# Sensact_v4_1.net
KiCad netlist of a schematic drawn in EAGLE
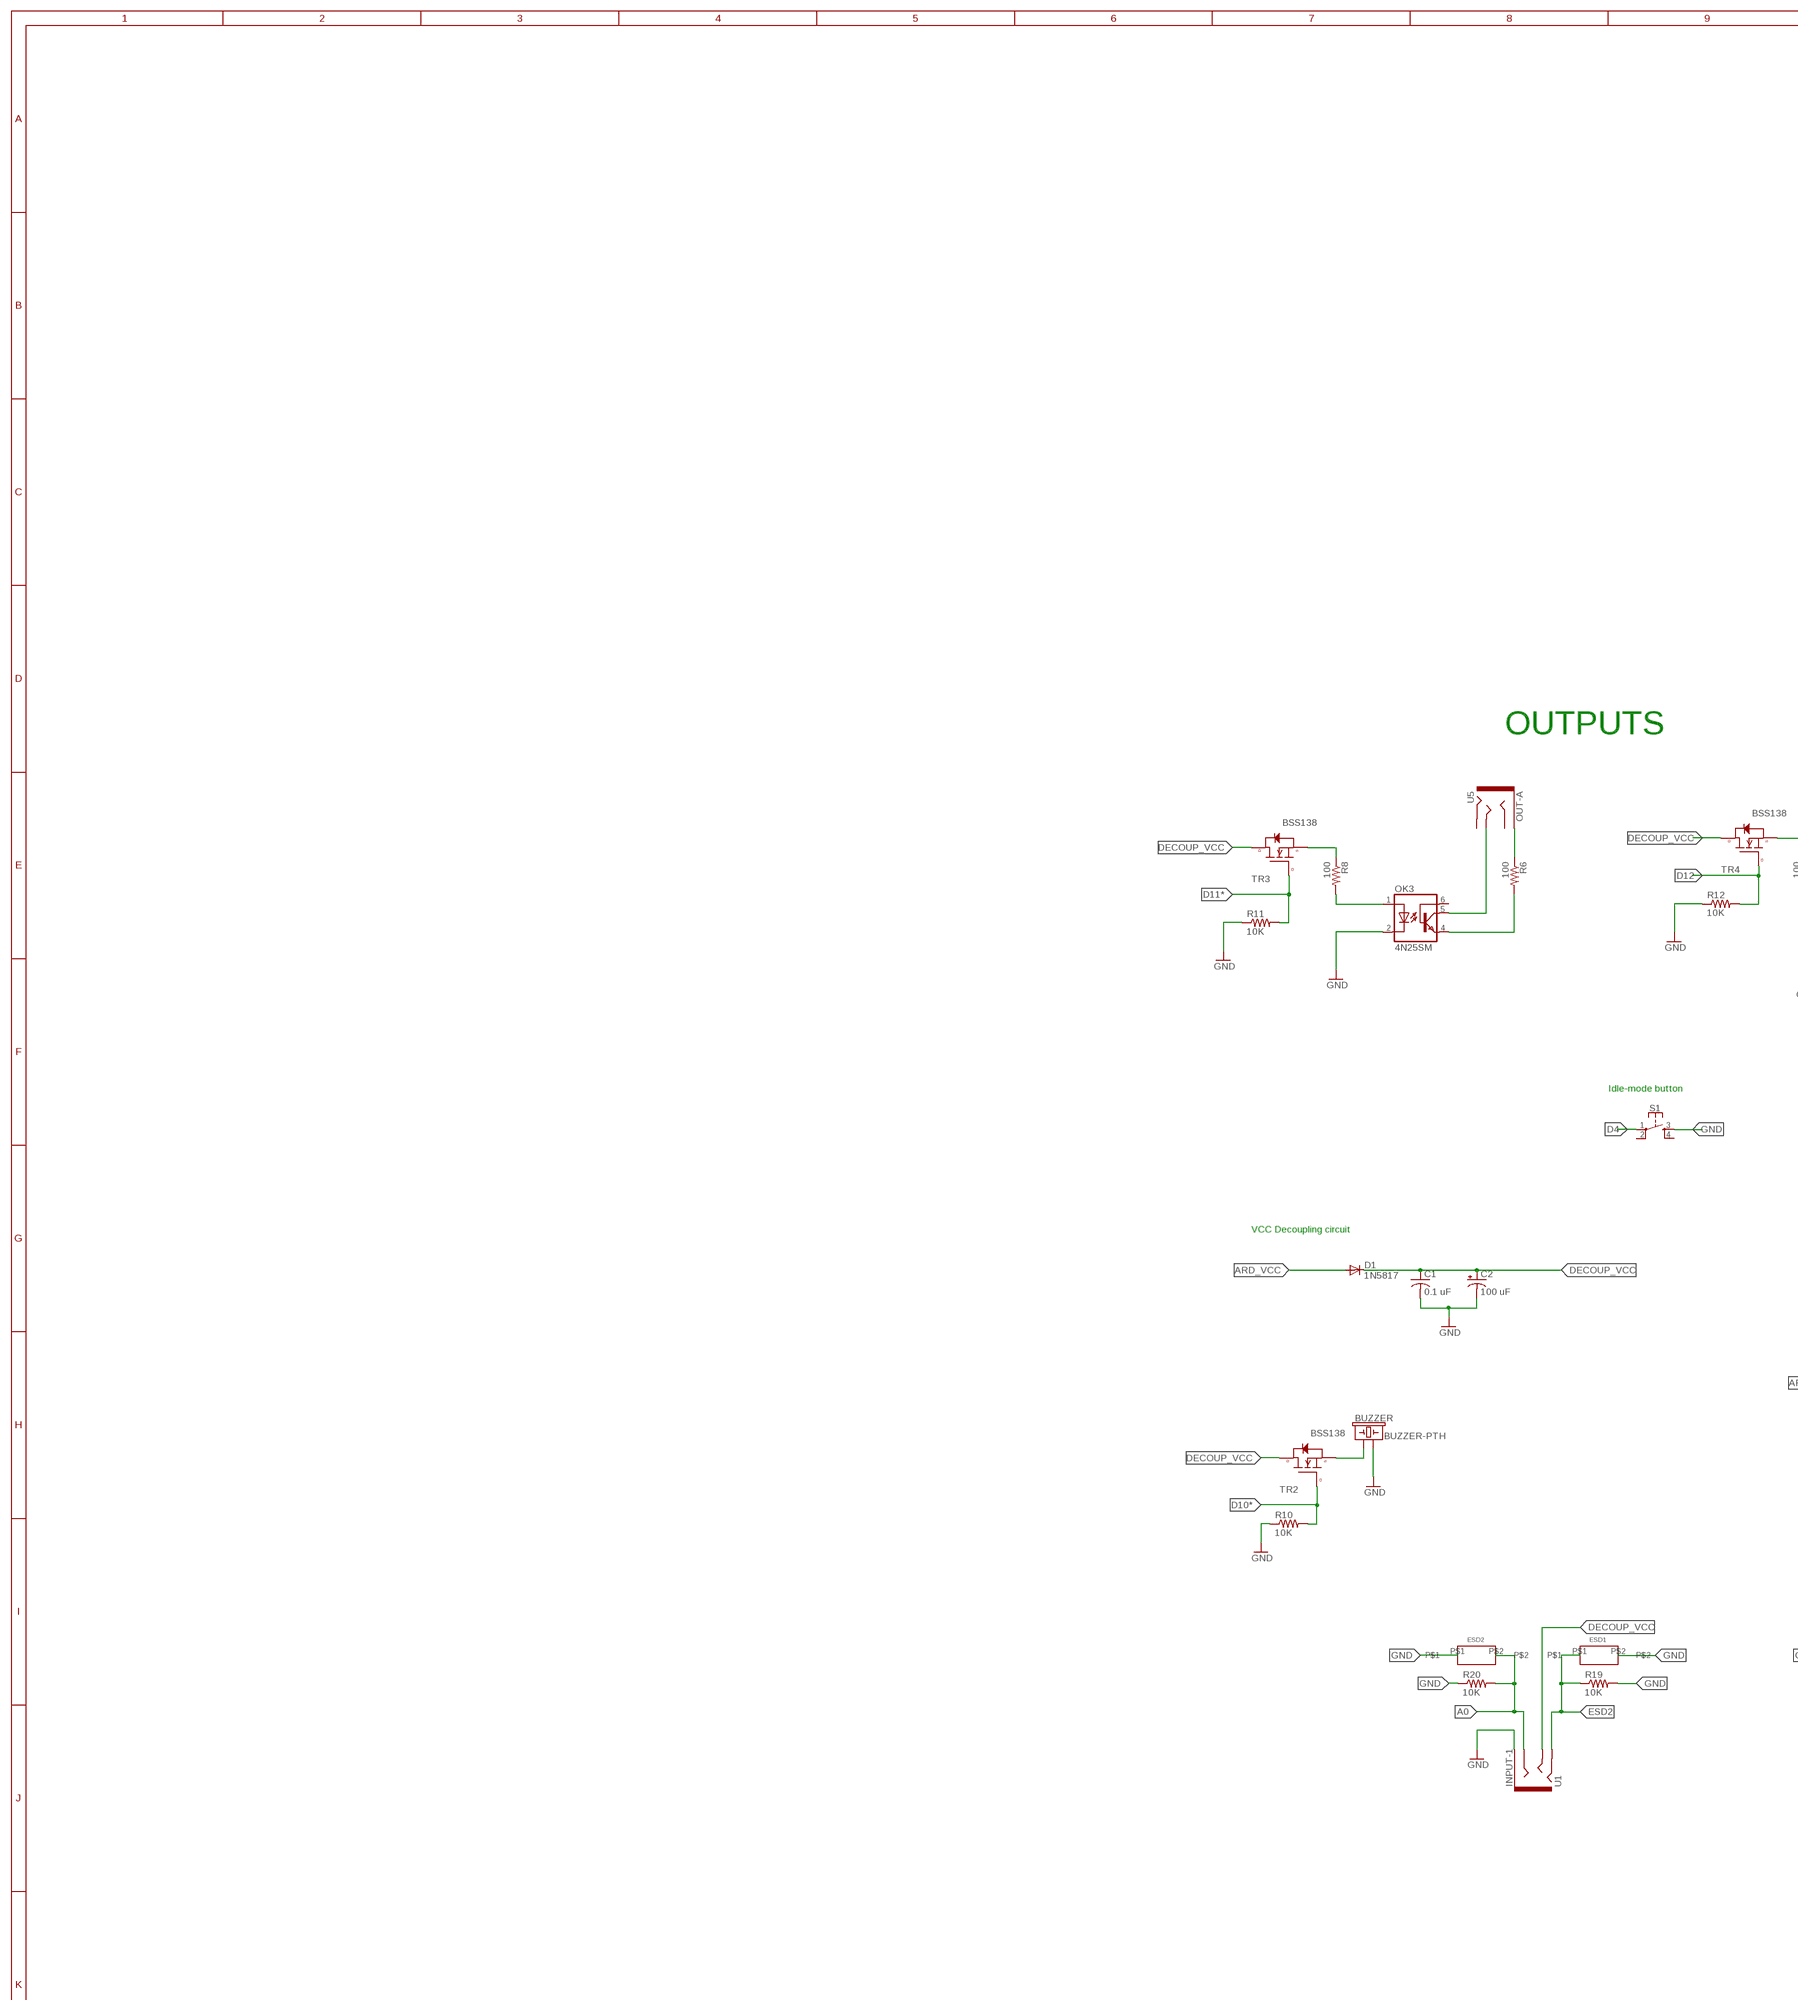
[diagram p0: schematic, sheet 1, part 1 of 3]
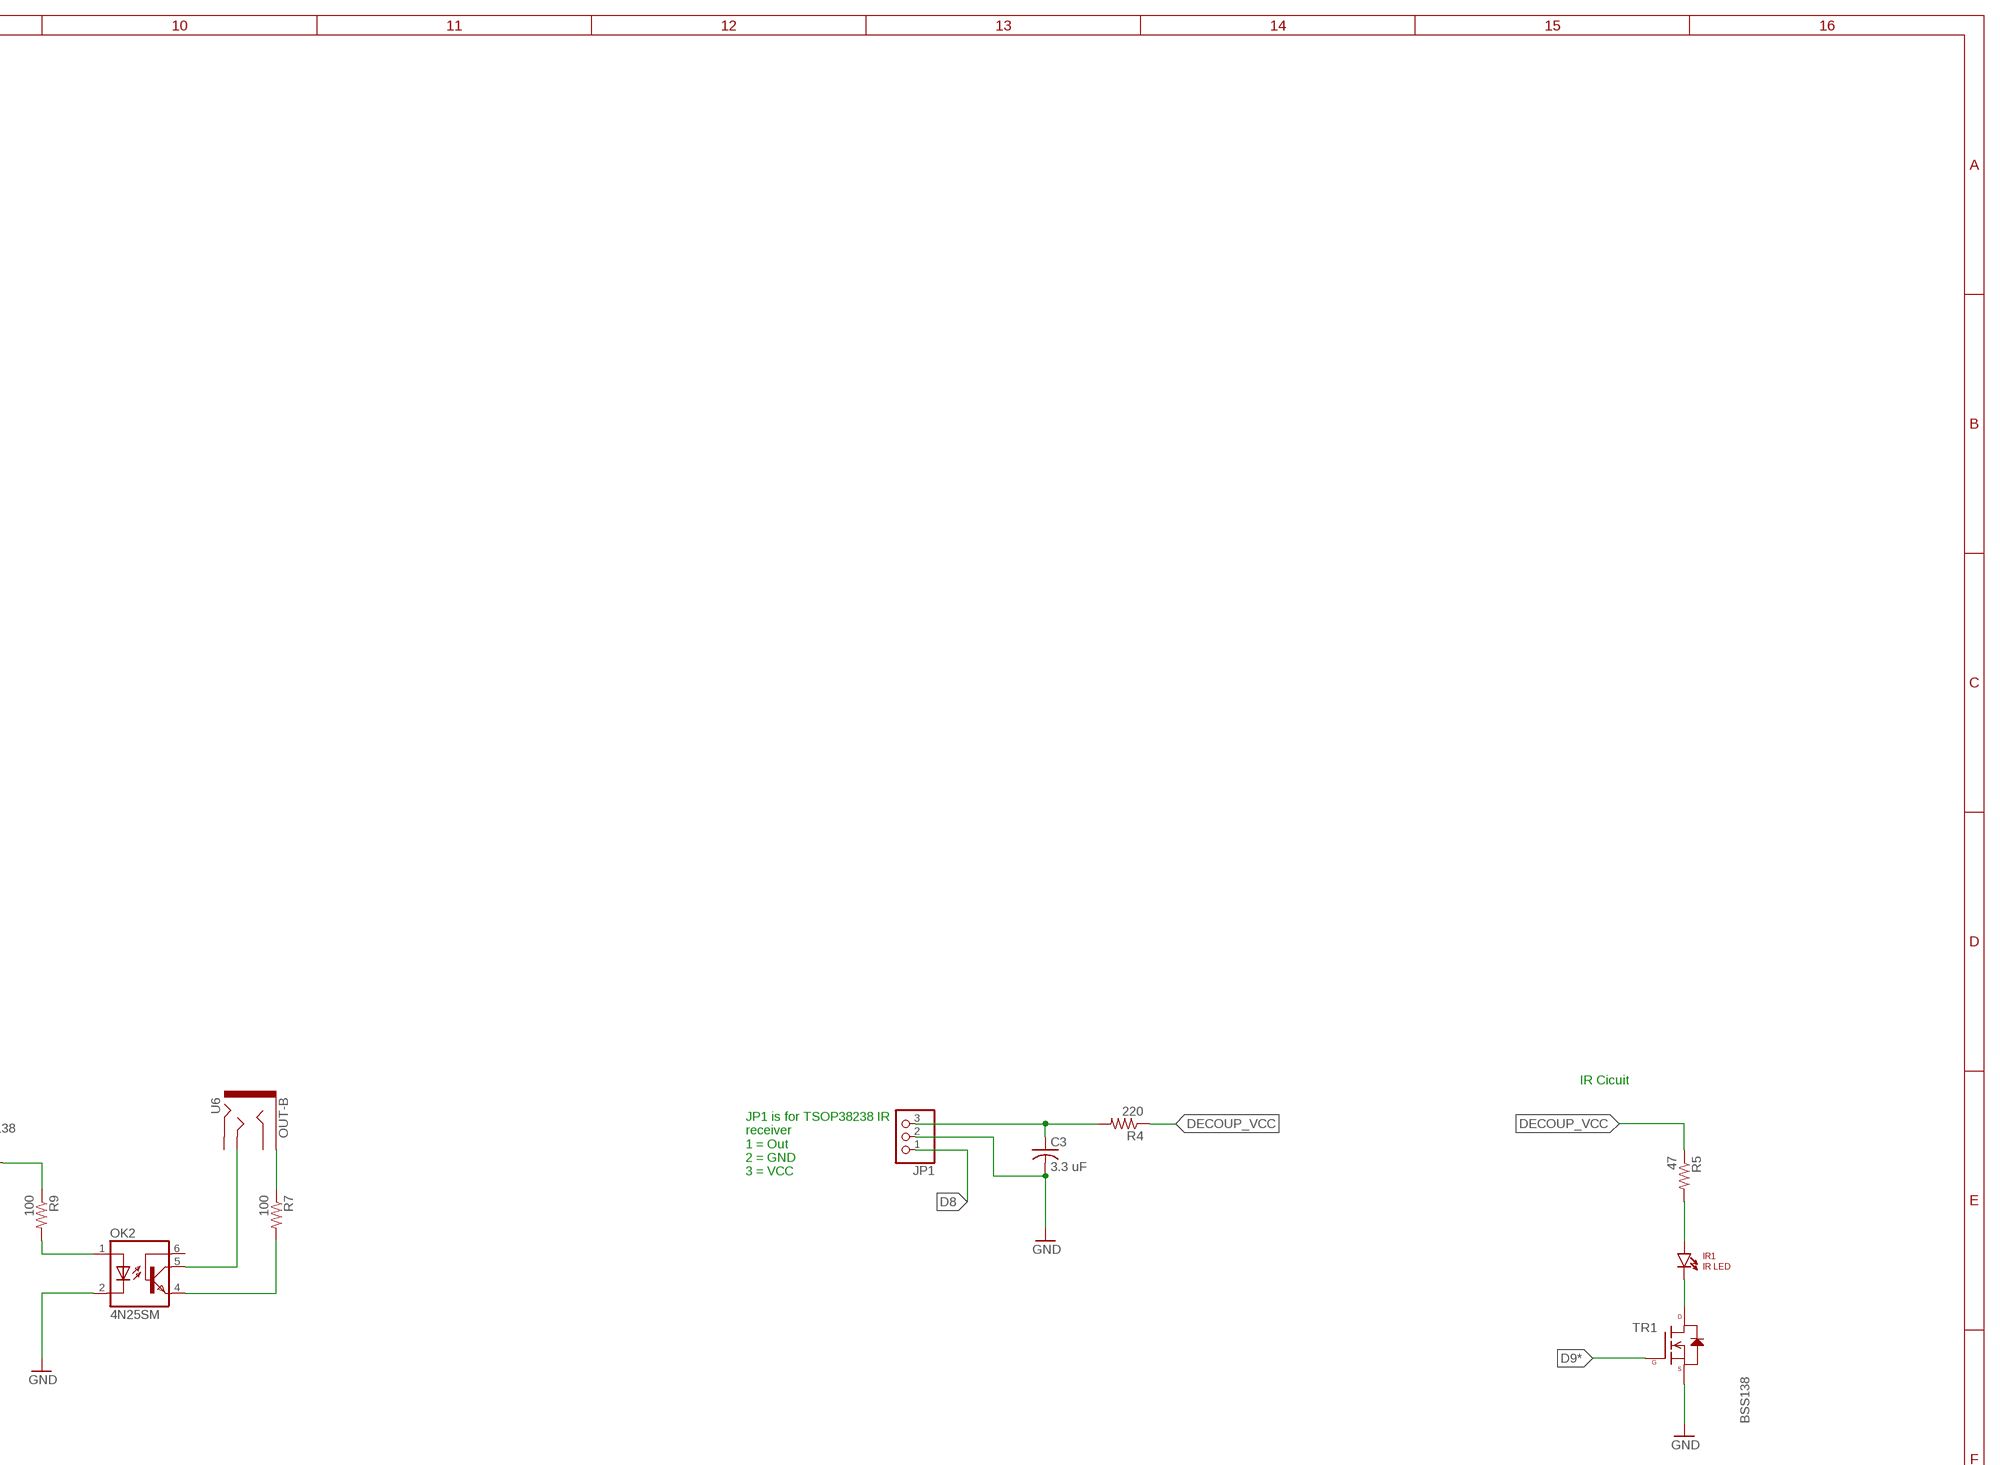
[diagram p1: schematic, sheet 1, part 2 of 3]
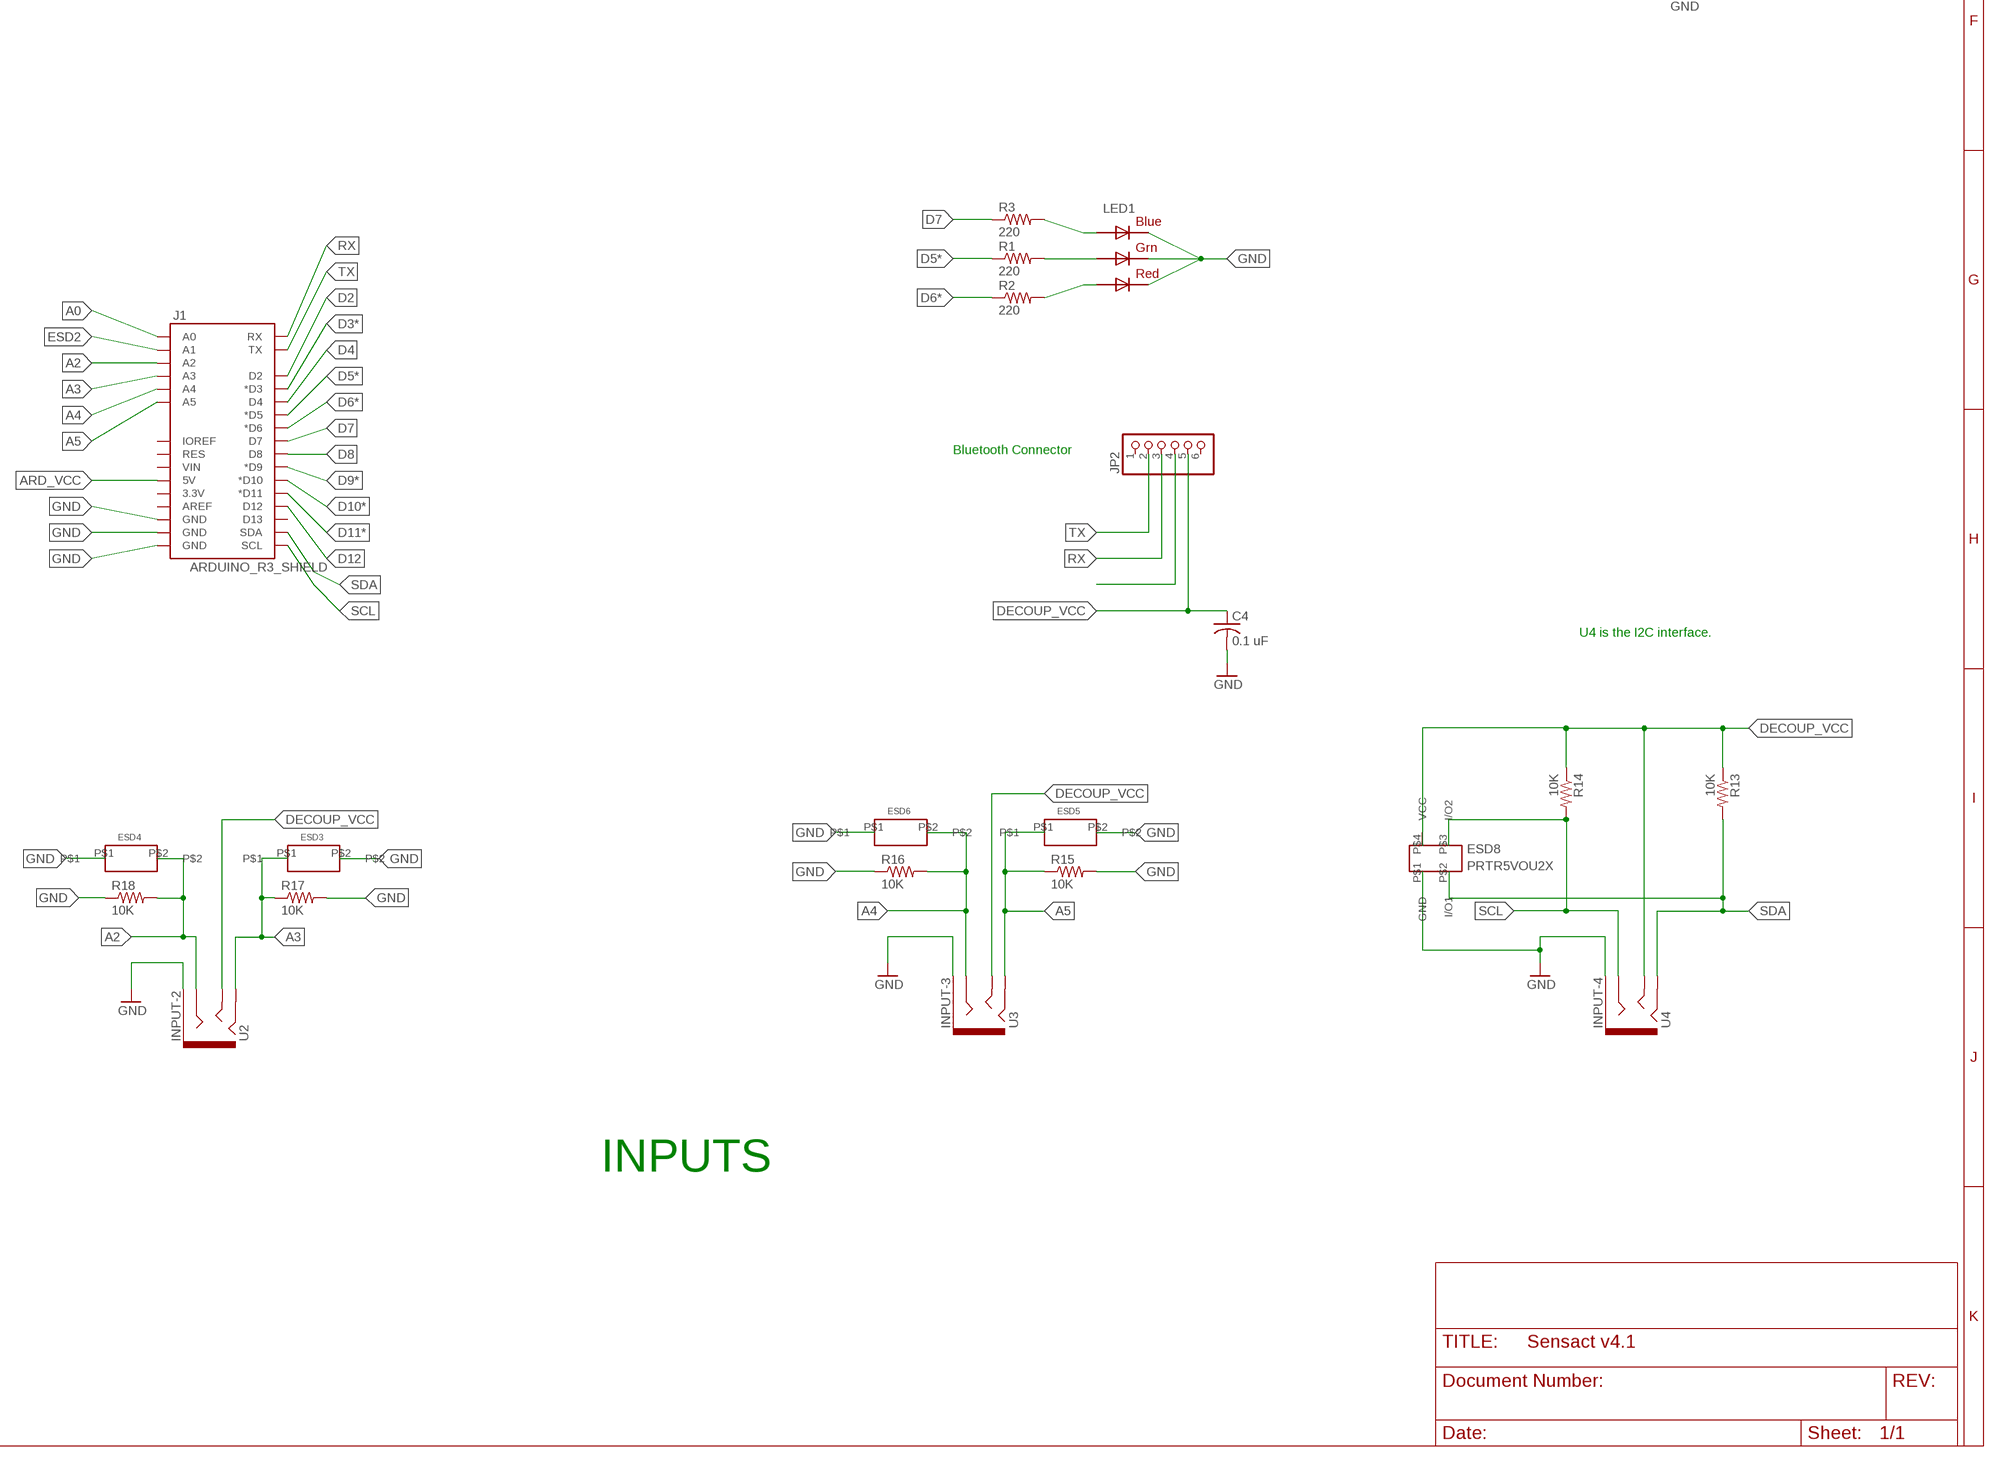
[diagram p2: schematic, sheet 1, part 3 of 3]

(export (version "E")
  (design (tool "Eeschema 10.0.6"))
  (components
    (comp (ref "BUZZER")
      (value "BUZZER-PTH")
      (footprint "eagle-import:BUZZER-12MM")
      (libsource (lib "eagle-import") (part "BUZZER-PTH"))
    )
    (comp (ref "C1")
      (value "0.1 uF")
      (footprint "eagle-import:C0805")
      (libsource (lib "eagle-import") (part "C-USC0805"))
    )
    (comp (ref "C2")
      (value "100 uF")
      (footprint "eagle-import:PANASONIC_C")
      (libsource (lib "eagle-import") (part "CAP_POLC"))
    )
    (comp (ref "C3")
      (value "3.3 uF")
      (footprint "eagle-import:C0805")
      (libsource (lib "eagle-import") (part "C-USC0805"))
    )
    (comp (ref "C4")
      (value "0.1 uF")
      (footprint "eagle-import:C0805")
      (libsource (lib "eagle-import") (part "C-USC0805"))
    )
    (comp (ref "D1")
      (value "1N5817")
      (footprint "eagle-import:DO214AC")
      (libsource (lib "eagle-import") (part "DIODE-DO214AC"))
    )
    (comp (ref "ESD1")
      (value "PESD5V0S1BA")
      (footprint "eagle-import:SOD323")
      (libsource (lib "eagle-import") (part "PESD5V0S1BA"))
    )
    (comp (ref "ESD2")
      (value "PESD5V0S1BA")
      (footprint "eagle-import:SOD323")
      (libsource (lib "eagle-import") (part "PESD5V0S1BA"))
    )
    (comp (ref "ESD3")
      (value "PESD5V0S1BA")
      (footprint "eagle-import:SOD323")
      (libsource (lib "eagle-import") (part "PESD5V0S1BA"))
    )
    (comp (ref "ESD4")
      (value "PESD5V0S1BA")
      (footprint "eagle-import:SOD323")
      (libsource (lib "eagle-import") (part "PESD5V0S1BA"))
    )
    (comp (ref "ESD5")
      (value "PESD5V0S1BA")
      (footprint "eagle-import:SOD323")
      (libsource (lib "eagle-import") (part "PESD5V0S1BA"))
    )
    (comp (ref "ESD6")
      (value "PESD5V0S1BA")
      (footprint "eagle-import:SOD323")
      (libsource (lib "eagle-import") (part "PESD5V0S1BA"))
    )
    (comp (ref "ESD8")
      (value "PRTR5VOU2X")
      (footprint "eagle-import:215")
      (libsource (lib "eagle-import") (part "PRTR5VOU2X"))
    )
    (comp (ref "INPUT-1")
      (value "U1")
      (footprint "eagle-import:AUDIO-JACK-TRRS-THRUHOLE")
      (libsource (lib "eagle-import") (part "AUDIO-JACK-TRRS-THRUHOLE"))
    )
    (comp (ref "INPUT-2")
      (value "U2")
      (footprint "eagle-import:AUDIO-JACK-TRRS-THRUHOLE")
      (libsource (lib "eagle-import") (part "AUDIO-JACK-TRRS-THRUHOLE"))
    )
    (comp (ref "INPUT-3")
      (value "U3")
      (footprint "eagle-import:AUDIO-JACK-TRRS-THRUHOLE")
      (libsource (lib "eagle-import") (part "AUDIO-JACK-TRRS-THRUHOLE"))
    )
    (comp (ref "INPUT-4")
      (value "U4")
      (footprint "eagle-import:AUDIO-JACK-TRRS-THRUHOLE")
      (libsource (lib "eagle-import") (part "AUDIO-JACK-TRRS-THRUHOLE"))
    )
    (comp (ref "IR1")
      (value "IR LED")
      (footprint "eagle-import:LTE-302")
      (libsource (lib "eagle-import") (part "LTE-302"))
    )
    (comp (ref "J1")
      (value "ARDUINO_R3_SHIELD")
      (footprint "eagle-import:UNO_R3_SHIELD")
      (libsource (lib "eagle-import") (part "ARDUINO_R3_SHIELD"))
    )
    (comp (ref "JP1")
      (value "PINHD-1X3")
      (footprint "eagle-import:1X03")
      (libsource (lib "eagle-import") (part "PINHD-1X3"))
    )
    (comp (ref "JP2")
      (value "PINHD-1X6")
      (footprint "eagle-import:1X06")
      (libsource (lib "eagle-import") (part "PINHD-1X6"))
    )
    (comp (ref "LED1")
      (value "RGBLED5050")
      (footprint "eagle-import:RGBLED5050")
      (libsource (lib "eagle-import") (part "RGBLED5050"))
    )
    (comp (ref "OK2")
      (value "4N25SM")
      (footprint "eagle-import:DIL6-SMD")
      (fields (field (name "MF") "FAIRCHILD SEMICONDUCTOR"))
      (libsource (lib "eagle-import") (part "4N?MS25"))
    )
    (comp (ref "OK3")
      (value "4N25SM")
      (footprint "eagle-import:DIL6-SMD")
      (fields (field (name "MF") "FAIRCHILD SEMICONDUCTOR"))
      (libsource (lib "eagle-import") (part "4N?MS25"))
    )
    (comp (ref "OUT-A")
      (value "U5")
      (footprint "eagle-import:AUDIO-JACK-TRRS-THRUHOLE")
      (libsource (lib "eagle-import") (part "AUDIO-JACK-TRRS-THRUHOLE"))
    )
    (comp (ref "OUT-B")
      (value "U6")
      (footprint "eagle-import:AUDIO-JACK-TRRS-THRUHOLE")
      (libsource (lib "eagle-import") (part "AUDIO-JACK-TRRS-THRUHOLE"))
    )
    (comp (ref "R1")
      (value "220")
      (footprint "eagle-import:0805")
      (libsource (lib "eagle-import") (part "RESISTOR0805-RES"))
    )
    (comp (ref "R2")
      (value "220")
      (footprint "eagle-import:0805")
      (libsource (lib "eagle-import") (part "RESISTOR0805-RES"))
    )
    (comp (ref "R3")
      (value "220")
      (footprint "eagle-import:0805")
      (libsource (lib "eagle-import") (part "RESISTOR0805-RES"))
    )
    (comp (ref "R4")
      (value "220")
      (footprint "eagle-import:0805")
      (libsource (lib "eagle-import") (part "RESISTOR0805-RES"))
    )
    (comp (ref "R5")
      (value "47")
      (footprint "eagle-import:0805")
      (libsource (lib "eagle-import") (part "RESISTOR0805-RES"))
    )
    (comp (ref "R6")
      (value "100")
      (footprint "eagle-import:0805")
      (libsource (lib "eagle-import") (part "RESISTOR0805-RES"))
    )
    (comp (ref "R7")
      (value "100")
      (footprint "eagle-import:0805")
      (libsource (lib "eagle-import") (part "RESISTOR0805-RES"))
    )
    (comp (ref "R8")
      (value "100")
      (footprint "eagle-import:0805")
      (libsource (lib "eagle-import") (part "RESISTOR0805-RES"))
    )
    (comp (ref "R9")
      (value "100")
      (footprint "eagle-import:0805")
      (libsource (lib "eagle-import") (part "RESISTOR0805-RES"))
    )
    (comp (ref "R10")
      (value "10K")
      (footprint "eagle-import:0805")
      (libsource (lib "eagle-import") (part "RESISTOR0805-RES"))
    )
    (comp (ref "R11")
      (value "10K")
      (footprint "eagle-import:0805")
      (libsource (lib "eagle-import") (part "RESISTOR0805-RES"))
    )
    (comp (ref "R12")
      (value "10K")
      (footprint "eagle-import:0805")
      (libsource (lib "eagle-import") (part "RESISTOR0805-RES"))
    )
    (comp (ref "R13")
      (value "10K")
      (footprint "eagle-import:0805")
      (libsource (lib "eagle-import") (part "RESISTOR0805-RES"))
    )
    (comp (ref "R14")
      (value "10K")
      (footprint "eagle-import:0805")
      (libsource (lib "eagle-import") (part "RESISTOR0805-RES"))
    )
    (comp (ref "R15")
      (value "10K")
      (footprint "eagle-import:0805")
      (libsource (lib "eagle-import") (part "RESISTOR0805-RES"))
    )
    (comp (ref "R16")
      (value "10K")
      (footprint "eagle-import:0805")
      (libsource (lib "eagle-import") (part "RESISTOR0805-RES"))
    )
    (comp (ref "R17")
      (value "10K")
      (footprint "eagle-import:0805")
      (libsource (lib "eagle-import") (part "RESISTOR0805-RES"))
    )
    (comp (ref "R18")
      (value "10K")
      (footprint "eagle-import:0805")
      (libsource (lib "eagle-import") (part "RESISTOR0805-RES"))
    )
    (comp (ref "R19")
      (value "10K")
      (footprint "eagle-import:0805")
      (libsource (lib "eagle-import") (part "RESISTOR0805-RES"))
    )
    (comp (ref "R20")
      (value "10K")
      (footprint "eagle-import:0805")
      (libsource (lib "eagle-import") (part "RESISTOR0805-RES"))
    )
    (comp (ref "S1")
      (value "MOMENTARY-SWITCH-SPST-2-SMD-4.6X2.8MM")
      (footprint "eagle-import:TACTILE_SWITCH_SMD_4.6X2.8MM")
      (libsource (lib "eagle-import") (part "MOMENTARY-SWITCH-SPST-2-SMD-4.6X2.8MM"))
    )
    (comp (ref "TR1")
      (value "BSS138")
      (footprint "eagle-import:SOT23-3")
      (libsource (lib "eagle-import") (part "N-CHANNEL-MOSFET-BSS138"))
    )
    (comp (ref "TR2")
      (value "BSS138")
      (footprint "eagle-import:SOT23-3")
      (libsource (lib "eagle-import") (part "N-CHANNEL-MOSFET-BSS138"))
    )
    (comp (ref "TR3")
      (value "BSS138")
      (footprint "eagle-import:SOT23-3")
      (libsource (lib "eagle-import") (part "N-CHANNEL-MOSFET-BSS138"))
    )
    (comp (ref "TR4")
      (value "BSS138")
      (footprint "eagle-import:SOT23-3")
      (libsource (lib "eagle-import") (part "N-CHANNEL-MOSFET-BSS138"))
    )
  )
  (nets
    (net (code "1") (name "A0") (class "Default")
      (node (ref "ESD2") (pin "P$2") (pinfunction "P$2_P$2") (pintype "bidirectional"))
      (node (ref "INPUT-1") (pin "RING1") (pinfunction "RING1_RING1") (pintype "bidirectional"))
      (node (ref "J1") (pin "A0") (pinfunction "A0_A0") (pintype "bidirectional"))
      (node (ref "R20") (pin "2") (pinfunction "2_2") (pintype "passive"))
    )
    (net (code "2") (name "A2") (class "Default")
      (node (ref "ESD4") (pin "P$2") (pinfunction "P$2_P$2") (pintype "bidirectional"))
      (node (ref "INPUT-2") (pin "RING1") (pinfunction "RING1_RING1") (pintype "bidirectional"))
      (node (ref "J1") (pin "A2") (pinfunction "A2_A2") (pintype "bidirectional"))
      (node (ref "R18") (pin "2") (pinfunction "2_2") (pintype "passive"))
    )
    (net (code "3") (name "A3") (class "Default")
      (node (ref "ESD3") (pin "P$1") (pinfunction "P$1_P$1") (pintype "bidirectional"))
      (node (ref "INPUT-2") (pin "RING2") (pinfunction "RING2_RING2") (pintype "bidirectional"))
      (node (ref "J1") (pin "A3") (pinfunction "A3_A3") (pintype "bidirectional"))
      (node (ref "R17") (pin "1") (pinfunction "1_1") (pintype "passive"))
    )
    (net (code "4") (name "A4") (class "Default")
      (node (ref "ESD6") (pin "P$2") (pinfunction "P$2_P$2") (pintype "bidirectional"))
      (node (ref "INPUT-3") (pin "RING1") (pinfunction "RING1_RING1") (pintype "bidirectional"))
      (node (ref "J1") (pin "A4") (pinfunction "A4_A4") (pintype "bidirectional"))
      (node (ref "R16") (pin "2") (pinfunction "2_2") (pintype "passive"))
    )
    (net (code "5") (name "A5") (class "Default")
      (node (ref "ESD5") (pin "P$1") (pinfunction "P$1_P$1") (pintype "bidirectional"))
      (node (ref "INPUT-3") (pin "RING2") (pinfunction "RING2_RING2") (pintype "bidirectional"))
      (node (ref "J1") (pin "A5") (pinfunction "A5_A5") (pintype "bidirectional"))
      (node (ref "R15") (pin "1") (pinfunction "1_1") (pintype "passive"))
    )
    (net (code "6") (name "ARD_VCC") (class "Default")
      (node (ref "D1") (pin "A") (pinfunction "A_A") (pintype "passive"))
      (node (ref "J1") (pin "5V") (pinfunction "5V_5V") (pintype "bidirectional"))
    )
    (net (code "7") (name "D2") (class "Default")
      (node (ref "J1") (pin "D2") (pinfunction "D2_D2") (pintype "bidirectional"))
    )
    (net (code "8") (name "D3*") (class "Default")
      (node (ref "J1") (pin "D3") (pinfunction "*D3_D3") (pintype "bidirectional"))
    )
    (net (code "9") (name "D4") (class "Default")
      (node (ref "J1") (pin "D4") (pinfunction "D4_D4") (pintype "bidirectional"))
      (node (ref "S1") (pin "1") (pinfunction "1_1") (pintype "passive"))
    )
    (net (code "10") (name "D5*") (class "Default")
      (node (ref "J1") (pin "D5") (pinfunction "*D5_D5") (pintype "bidirectional"))
      (node (ref "R1") (pin "1") (pinfunction "1_1") (pintype "passive"))
    )
    (net (code "11") (name "D6*") (class "Default")
      (node (ref "J1") (pin "D6") (pinfunction "*D6_D6") (pintype "bidirectional"))
      (node (ref "R2") (pin "1") (pinfunction "1_1") (pintype "passive"))
    )
    (net (code "12") (name "D7") (class "Default")
      (node (ref "J1") (pin "D7") (pinfunction "D7_D7") (pintype "bidirectional"))
      (node (ref "R3") (pin "1") (pinfunction "1_1") (pintype "passive"))
    )
    (net (code "13") (name "D8") (class "Default")
      (node (ref "J1") (pin "D8") (pinfunction "D8_D8") (pintype "bidirectional"))
      (node (ref "JP1") (pin "1") (pinfunction "1_1") (pintype "passive"))
    )
    (net (code "14") (name "D9*") (class "Default")
      (node (ref "J1") (pin "D9") (pinfunction "*D9_D9") (pintype "bidirectional"))
      (node (ref "TR1") (pin "1") (pinfunction "G_1") (pintype "passive"))
    )
    (net (code "15") (name "D10*") (class "Default")
      (node (ref "J1") (pin "D10") (pinfunction "*D10_D10") (pintype "bidirectional"))
      (node (ref "R10") (pin "2") (pinfunction "2_2") (pintype "passive"))
      (node (ref "TR2") (pin "1") (pinfunction "G_1") (pintype "passive"))
    )
    (net (code "16") (name "D11*") (class "Default")
      (node (ref "J1") (pin "D11") (pinfunction "*D11_D11") (pintype "bidirectional"))
      (node (ref "R11") (pin "2") (pinfunction "2_2") (pintype "passive"))
      (node (ref "TR3") (pin "1") (pinfunction "G_1") (pintype "passive"))
    )
    (net (code "17") (name "D12") (class "Default")
      (node (ref "J1") (pin "D12") (pinfunction "D12_D12") (pintype "bidirectional"))
      (node (ref "R12") (pin "2") (pinfunction "2_2") (pintype "passive"))
      (node (ref "TR4") (pin "1") (pinfunction "G_1") (pintype "passive"))
    )
    (net (code "18") (name "DECOUP_VCC") (class "Default")
      (node (ref "C1") (pin "1") (pinfunction "1_1") (pintype "passive"))
      (node (ref "C2") (pin "+") (pinfunction "+_+") (pintype "passive"))
      (node (ref "C4") (pin "1") (pinfunction "1_1") (pintype "passive"))
      (node (ref "D1") (pin "C") (pinfunction "C_C") (pintype "passive"))
      (node (ref "ESD8") (pin "P$4") (pinfunction "VCC_P$4") (pintype "bidirectional"))
      (node (ref "INPUT-1") (pin "TIP") (pinfunction "TIP_TIP") (pintype "bidirectional"))
      (node (ref "INPUT-2") (pin "TIP") (pinfunction "TIP_TIP") (pintype "bidirectional"))
      (node (ref "INPUT-3") (pin "TIP") (pinfunction "TIP_TIP") (pintype "bidirectional"))
      (node (ref "INPUT-4") (pin "TIP") (pinfunction "TIP_TIP") (pintype "bidirectional"))
      (node (ref "JP2") (pin "5") (pinfunction "5_5") (pintype "passive"))
      (node (ref "R13") (pin "1") (pinfunction "1_1") (pintype "passive"))
      (node (ref "R14") (pin "1") (pinfunction "1_1") (pintype "passive"))
      (node (ref "R4") (pin "1") (pinfunction "1_1") (pintype "passive"))
      (node (ref "R5") (pin "1") (pinfunction "1_1") (pintype "passive"))
      (node (ref "TR2") (pin "3") (pinfunction "D_3") (pintype "passive"))
      (node (ref "TR3") (pin "3") (pinfunction "D_3") (pintype "passive"))
      (node (ref "TR4") (pin "3") (pinfunction "D_3") (pintype "passive"))
    )
    (net (code "19") (name "ESD2") (class "Default")
      (node (ref "ESD1") (pin "P$1") (pinfunction "P$1_P$1") (pintype "bidirectional"))
      (node (ref "INPUT-1") (pin "RING2") (pinfunction "RING2_RING2") (pintype "bidirectional"))
      (node (ref "J1") (pin "A1") (pinfunction "A1_A1") (pintype "bidirectional"))
      (node (ref "R19") (pin "1") (pinfunction "1_1") (pintype "passive"))
    )
    (net (code "20") (name "GND") (class "Default")
      (node (ref "BUZZER") (pin "-") (pinfunction "2_-") (pintype "passive"))
      (node (ref "C1") (pin "2") (pinfunction "2_2") (pintype "passive"))
      (node (ref "C2") (pin "-") (pinfunction "-_-") (pintype "passive"))
      (node (ref "C3") (pin "2") (pinfunction "2_2") (pintype "passive"))
      (node (ref "C4") (pin "2") (pinfunction "2_2") (pintype "passive"))
      (node (ref "ESD1") (pin "P$2") (pinfunction "P$2_P$2") (pintype "bidirectional"))
      (node (ref "ESD2") (pin "P$1") (pinfunction "P$1_P$1") (pintype "bidirectional"))
      (node (ref "ESD3") (pin "P$2") (pinfunction "P$2_P$2") (pintype "bidirectional"))
      (node (ref "ESD4") (pin "P$1") (pinfunction "P$1_P$1") (pintype "bidirectional"))
      (node (ref "ESD5") (pin "P$2") (pinfunction "P$2_P$2") (pintype "bidirectional"))
      (node (ref "ESD6") (pin "P$1") (pinfunction "P$1_P$1") (pintype "bidirectional"))
      (node (ref "ESD8") (pin "P$1") (pinfunction "GND_P$1") (pintype "bidirectional"))
      (node (ref "INPUT-1") (pin "SLEEVE") (pinfunction "EARTH_SLEEVE") (pintype "bidirectional"))
      (node (ref "INPUT-2") (pin "SLEEVE") (pinfunction "EARTH_SLEEVE") (pintype "bidirectional"))
      (node (ref "INPUT-3") (pin "SLEEVE") (pinfunction "EARTH_SLEEVE") (pintype "bidirectional"))
      (node (ref "INPUT-4") (pin "SLEEVE") (pinfunction "EARTH_SLEEVE") (pintype "bidirectional"))
      (node (ref "J1") (pin "GND@0") (pinfunction "GND_GND@0") (pintype "bidirectional"))
      (node (ref "J1") (pin "GND@1") (pinfunction "GND_GND@1") (pintype "bidirectional"))
      (node (ref "J1") (pin "GND@2") (pinfunction "GND_GND@2") (pintype "bidirectional"))
      (node (ref "JP1") (pin "2") (pinfunction "2_2") (pintype "passive"))
      (node (ref "JP2") (pin "4") (pinfunction "4_4") (pintype "passive"))
      (node (ref "LED1") (pin "4") (pinfunction "BLUE_C_4") (pintype "bidirectional"))
      (node (ref "LED1") (pin "5") (pinfunction "RED_C_5") (pintype "bidirectional"))
      (node (ref "LED1") (pin "6") (pinfunction "GREEN_C_6") (pintype "bidirectional"))
      (node (ref "OK2") (pin "2") (pinfunction "C_2") (pintype "passive"))
      (node (ref "OK3") (pin "2") (pinfunction "C_2") (pintype "passive"))
      (node (ref "R10") (pin "1") (pinfunction "1_1") (pintype "passive"))
      (node (ref "R11") (pin "1") (pinfunction "1_1") (pintype "passive"))
      (node (ref "R12") (pin "1") (pinfunction "1_1") (pintype "passive"))
      (node (ref "R15") (pin "2") (pinfunction "2_2") (pintype "passive"))
      (node (ref "R16") (pin "1") (pinfunction "1_1") (pintype "passive"))
      (node (ref "R17") (pin "2") (pinfunction "2_2") (pintype "passive"))
      (node (ref "R18") (pin "1") (pinfunction "1_1") (pintype "passive"))
      (node (ref "R19") (pin "2") (pinfunction "2_2") (pintype "passive"))
      (node (ref "R20") (pin "1") (pinfunction "1_1") (pintype "passive"))
      (node (ref "S1") (pin "3") (pinfunction "3_3") (pintype "passive"))
      (node (ref "TR1") (pin "2") (pinfunction "S_2") (pintype "passive"))
    )
    (net (code "21") (name "Net-(BUZZER-1)") (class "Default")
      (node (ref "BUZZER") (pin "+") (pinfunction "1_+") (pintype "passive"))
      (node (ref "TR2") (pin "2") (pinfunction "S_2") (pintype "passive"))
    )
    (net (code "22") (name "Net-(C3-Pad1)") (class "Default")
      (node (ref "C3") (pin "1") (pinfunction "1_1") (pintype "passive"))
      (node (ref "JP1") (pin "3") (pinfunction "3_3") (pintype "passive"))
      (node (ref "R4") (pin "2") (pinfunction "2_2") (pintype "passive"))
    )
    (net (code "23") (name "Net-(IR1-PadA)") (class "Default")
      (node (ref "IR1") (pin "A") (pinfunction "A_A") (pintype "bidirectional"))
      (node (ref "R5") (pin "2") (pinfunction "2_2") (pintype "passive"))
    )
    (net (code "24") (name "Net-(LED1-BLUE_A)") (class "Default")
      (node (ref "LED1") (pin "3") (pinfunction "BLUE_A_3") (pintype "bidirectional"))
      (node (ref "R3") (pin "2") (pinfunction "2_2") (pintype "passive"))
    )
    (net (code "25") (name "Net-(LED1-GREEN_A)") (class "Default")
      (node (ref "LED1") (pin "1") (pinfunction "GREEN_A_1") (pintype "bidirectional"))
      (node (ref "R1") (pin "2") (pinfunction "2_2") (pintype "passive"))
    )
    (net (code "26") (name "Net-(LED1-RED_A)") (class "Default")
      (node (ref "LED1") (pin "2") (pinfunction "RED_A_2") (pintype "bidirectional"))
      (node (ref "R2") (pin "2") (pinfunction "2_2") (pintype "passive"))
    )
    (net (code "27") (name "Net-(OK2-A)") (class "Default")
      (node (ref "OK2") (pin "1") (pinfunction "A_1") (pintype "passive"))
      (node (ref "R9") (pin "2") (pinfunction "2_2") (pintype "passive"))
    )
    (net (code "28") (name "Net-(OK2-COL)") (class "Default")
      (node (ref "OK2") (pin "5") (pinfunction "COL_5") (pintype "passive"))
      (node (ref "OUT-B") (pin "TIP") (pinfunction "TIP_TIP") (pintype "bidirectional"))
    )
    (net (code "29") (name "Net-(OK2-EMI)") (class "Default")
      (node (ref "OK2") (pin "4") (pinfunction "EMI_4") (pintype "passive"))
      (node (ref "R7") (pin "2") (pinfunction "2_2") (pintype "passive"))
    )
    (net (code "30") (name "Net-(OK3-A)") (class "Default")
      (node (ref "OK3") (pin "1") (pinfunction "A_1") (pintype "passive"))
      (node (ref "R8") (pin "2") (pinfunction "2_2") (pintype "passive"))
    )
    (net (code "31") (name "Net-(OK3-COL)") (class "Default")
      (node (ref "OK3") (pin "5") (pinfunction "COL_5") (pintype "passive"))
      (node (ref "OUT-A") (pin "TIP") (pinfunction "TIP_TIP") (pintype "bidirectional"))
    )
    (net (code "32") (name "Net-(OK3-EMI)") (class "Default")
      (node (ref "OK3") (pin "4") (pinfunction "EMI_4") (pintype "passive"))
      (node (ref "R6") (pin "2") (pinfunction "2_2") (pintype "passive"))
    )
    (net (code "33") (name "Net-(OUT-A-EARTH)") (class "Default")
      (node (ref "OUT-A") (pin "SLEEVE") (pinfunction "EARTH_SLEEVE") (pintype "bidirectional"))
      (node (ref "R6") (pin "1") (pinfunction "1_1") (pintype "passive"))
    )
    (net (code "34") (name "Net-(OUT-B-EARTH)") (class "Default")
      (node (ref "OUT-B") (pin "SLEEVE") (pinfunction "EARTH_SLEEVE") (pintype "bidirectional"))
      (node (ref "R7") (pin "1") (pinfunction "1_1") (pintype "passive"))
    )
    (net (code "35") (name "Net-(TR1-D)") (class "Default")
      (node (ref "IR1") (pin "C") (pinfunction "C_C") (pintype "bidirectional"))
      (node (ref "TR1") (pin "3") (pinfunction "D_3") (pintype "passive"))
    )
    (net (code "36") (name "Net-(TR3-S)") (class "Default")
      (node (ref "R8") (pin "1") (pinfunction "1_1") (pintype "passive"))
      (node (ref "TR3") (pin "2") (pinfunction "S_2") (pintype "passive"))
    )
    (net (code "37") (name "Net-(TR4-S)") (class "Default")
      (node (ref "R9") (pin "1") (pinfunction "1_1") (pintype "passive"))
      (node (ref "TR4") (pin "2") (pinfunction "S_2") (pintype "passive"))
    )
    (net (code "38") (name "RX") (class "Default")
      (node (ref "J1") (pin "RX") (pinfunction "RX_RX") (pintype "bidirectional"))
      (node (ref "JP2") (pin "3") (pinfunction "3_3") (pintype "passive"))
    )
    (net (code "39") (name "SCL") (class "Default")
      (node (ref "ESD8") (pin "P$3") (pinfunction "I/O2_P$3") (pintype "bidirectional"))
      (node (ref "INPUT-4") (pin "RING1") (pinfunction "RING1_RING1") (pintype "bidirectional"))
      (node (ref "J1") (pin "SCL") (pinfunction "SCL_SCL") (pintype "bidirectional"))
      (node (ref "R14") (pin "2") (pinfunction "2_2") (pintype "passive"))
    )
    (net (code "40") (name "SDA") (class "Default")
      (node (ref "ESD8") (pin "P$2") (pinfunction "I/O1_P$2") (pintype "bidirectional"))
      (node (ref "INPUT-4") (pin "RING2") (pinfunction "RING2_RING2") (pintype "bidirectional"))
      (node (ref "J1") (pin "SDA") (pinfunction "SDA_SDA") (pintype "bidirectional"))
      (node (ref "R13") (pin "2") (pinfunction "2_2") (pintype "passive"))
    )
    (net (code "41") (name "TX") (class "Default")
      (node (ref "J1") (pin "TX") (pinfunction "TX_TX") (pintype "bidirectional"))
      (node (ref "JP2") (pin "2") (pinfunction "2_2") (pintype "passive"))
    )
    (net (code "42") (name "unconnected-(J1-Pad3.3V)") (class "Default")
      (node (ref "J1") (pin "3.3V") (pinfunction "3.3V_3.3V") (pintype "bidirectional"))
    )
    (net (code "43") (name "unconnected-(J1-PadAREF)") (class "Default")
      (node (ref "J1") (pin "AREF") (pinfunction "AREF_AREF") (pintype "bidirectional"))
    )
    (net (code "44") (name "unconnected-(J1-PadD13)") (class "Default")
      (node (ref "J1") (pin "D13") (pinfunction "D13_D13") (pintype "bidirectional"))
    )
    (net (code "45") (name "unconnected-(J1-PadIOREF)") (class "Default")
      (node (ref "J1") (pin "IOREF") (pinfunction "IOREF_IOREF") (pintype "bidirectional"))
    )
    (net (code "46") (name "unconnected-(J1-PadRES)") (class "Default")
      (node (ref "J1") (pin "RES") (pinfunction "RES_RES") (pintype "bidirectional"))
    )
    (net (code "47") (name "unconnected-(J1-PadVIN)") (class "Default")
      (node (ref "J1") (pin "VIN") (pinfunction "VIN_VIN") (pintype "bidirectional"))
    )
    (net (code "48") (name "unconnected-(JP2-Pad1)") (class "Default")
      (node (ref "JP2") (pin "1") (pinfunction "1_1") (pintype "passive"))
    )
    (net (code "49") (name "unconnected-(JP2-Pad6)") (class "Default")
      (node (ref "JP2") (pin "6") (pinfunction "6_6") (pintype "passive"))
    )
    (net (code "50") (name "unconnected-(OK2-BAS-Pad6)") (class "Default")
      (node (ref "OK2") (pin "6") (pinfunction "BAS_6") (pintype "passive"))
    )
    (net (code "51") (name "unconnected-(OK3-BAS-Pad6)") (class "Default")
      (node (ref "OK3") (pin "6") (pinfunction "BAS_6") (pintype "passive"))
    )
    (net (code "52") (name "unconnected-(OUT-A-PadRING1)") (class "Default")
      (node (ref "OUT-A") (pin "RING1") (pinfunction "RING1_RING1") (pintype "bidirectional"))
    )
    (net (code "53") (name "unconnected-(OUT-A-PadRING2)") (class "Default")
      (node (ref "OUT-A") (pin "RING2") (pinfunction "RING2_RING2") (pintype "bidirectional"))
    )
    (net (code "54") (name "unconnected-(OUT-B-PadRING1)") (class "Default")
      (node (ref "OUT-B") (pin "RING1") (pinfunction "RING1_RING1") (pintype "bidirectional"))
    )
    (net (code "55") (name "unconnected-(OUT-B-PadRING2)") (class "Default")
      (node (ref "OUT-B") (pin "RING2") (pinfunction "RING2_RING2") (pintype "bidirectional"))
    )
    (net (code "56") (name "unconnected-(S1-Pad2)") (class "Default")
      (node (ref "S1") (pin "2") (pinfunction "2_2") (pintype "passive"))
    )
    (net (code "57") (name "unconnected-(S1-Pad4)") (class "Default")
      (node (ref "S1") (pin "4") (pinfunction "4_4") (pintype "passive"))
    )
  )
)
